# FPGA_IO.net
KiCad netlist of a schematic drawn in Altium Designer
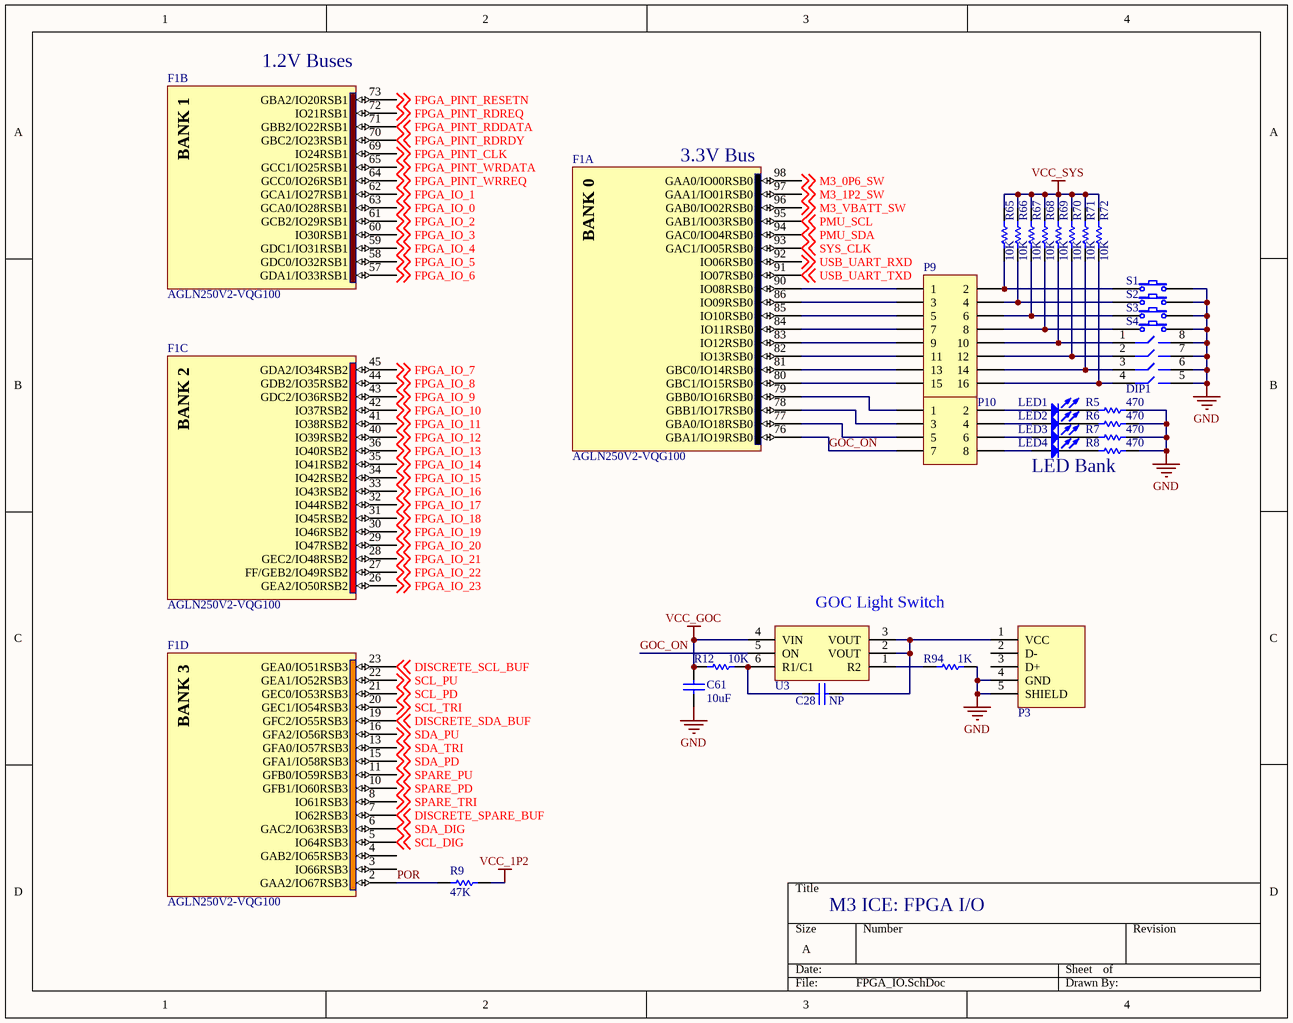
[diagram p0: FPGA_IO.SchDoc]

(export (version "E")
  (design (tool "Eeschema 10.0.6"))
  (components
    (comp (ref "C28")
      (value "NP")
      (footprint "0402")
      (description "Capacitor (Semiconductor SIM Model)")
      (fields (field (name "Comment") "Cap Semi") (field (name "PUBLISHER") "Altium Limited"))
      (libsource (lib "Miscellaneous Devices") (part "Cap Semi"))
    )
    (comp (ref "C61")
      (value "10uF")
      (footprint "0805")
      (description "Capacitor (Semiconductor SIM Model)")
      (fields
        (field (name "DISTPARTNO") "445-6857-1-ND")
        (field (name "MANPARTNO") "C2012X7R1A106K")
        (field (name "PUBLISHER") "Altium Limited")
      )
      (libsource (lib "M3") (part "Cap Chip"))
    )
    (comp (ref "DIP1")
      (value "ADE0404")
      (footprint "DIP-8")
      (description "4-DIP Switch")
      (fields (field (name "DISTPARTNO") "450-1364-ND"))
      (libsource (lib "M3") (part "ADE0404"))
    )
    (comp (ref "F1")
      (value "AGLN250V2-VQG100")
      (footprint "VQ100_N")
      (fields (field (name "DISTPARTNO") "1100-1134-ND") (field (name "PUBLISHER") "Altium Limited"))
      (libsource (lib "Actel IGLOO nano") (part "AGLN250V2-VQG100"))
    )
    (comp (ref "LED1")
      (value "LED 1206")
      (footprint "1206_LED")
      (fields (field (name "DISTPARTNO") "160-1169-1-ND") (field (name "MANPARTNO") "LTST-C150GKT"))
      (libsource (lib "M3") (part "LED 1206"))
    )
    (comp (ref "LED2")
      (value "LED 1206")
      (footprint "1206_LED")
      (fields (field (name "DISTPARTNO") "160-1169-1-ND") (field (name "MANPARTNO") "LTST-C150GKT"))
      (libsource (lib "M3") (part "LED 1206"))
    )
    (comp (ref "LED3")
      (value "LED 1206")
      (footprint "1206_LED")
      (fields (field (name "DISTPARTNO") "160-1169-1-ND") (field (name "MANPARTNO") "LTST-C150GKT"))
      (libsource (lib "M3") (part "LED 1206"))
    )
    (comp (ref "LED4")
      (value "LED 1206")
      (footprint "1206_LED")
      (fields (field (name "DISTPARTNO") "160-1169-1-ND") (field (name "MANPARTNO") "LTST-C150GKT"))
      (libsource (lib "M3") (part "LED 1206"))
    )
    (comp (ref "P3")
      (value "USB_HORIZONTAL")
      (footprint "USB_HORIZONTAL")
      (fields (field (name "DISTPARTNO") "A31726-ND") (field (name "MANPARTNO") "292303-1"))
      (libsource (lib "M3") (part "USB_HORIZONTAL"))
    )
    (comp (ref "P9")
      (value "Header 8X2")
      (footprint "HDR2X8")
      (description "Header, 8-Pin, Dual row")
      (fields (field (name "PUBLISHER") "Altium Limited"))
      (libsource (lib "Miscellaneous Connectors") (part "Header 8X2"))
    )
    (comp (ref "P10")
      (value "Header 4X2")
      (footprint "HDR2X4")
      (description "Header, 4-Pin, Dual row")
      (fields (field (name "PUBLISHER") "Altium Limited"))
      (libsource (lib "Miscellaneous Connectors") (part "Header 4X2"))
    )
    (comp (ref "R5")
      (value "470")
      (footprint "0603")
      (description "Semiconductor Resistor")
      (fields
        (field (name "DISTPARTNO") "P470GCT-ND")
        (field (name "MANPARTNO") "ERJ-3GEYJ471V")
        (field (name "PUBLISHER") "Altium Limited")
      )
      (libsource (lib "M3") (part "Res Chip"))
    )
    (comp (ref "R6")
      (value "470")
      (footprint "0603")
      (description "Semiconductor Resistor")
      (fields
        (field (name "DISTPARTNO") "P470GCT-ND")
        (field (name "MANPARTNO") "ERJ-3GEYJ471V")
        (field (name "PUBLISHER") "Altium Limited")
      )
      (libsource (lib "M3") (part "Res Chip"))
    )
    (comp (ref "R7")
      (value "470")
      (footprint "0603")
      (description "Semiconductor Resistor")
      (fields
        (field (name "DISTPARTNO") "P470GCT-ND")
        (field (name "MANPARTNO") "ERJ-3GEYJ471V")
        (field (name "PUBLISHER") "Altium Limited")
      )
      (libsource (lib "M3") (part "Res Chip"))
    )
    (comp (ref "R8")
      (value "470")
      (footprint "0603")
      (description "Semiconductor Resistor")
      (fields
        (field (name "DISTPARTNO") "P470GCT-ND")
        (field (name "MANPARTNO") "ERJ-3GEYJ471V")
        (field (name "PUBLISHER") "Altium Limited")
      )
      (libsource (lib "M3") (part "Res Chip"))
    )
    (comp (ref "R9")
      (value "47K")
      (footprint "0603")
      (description "Semiconductor Resistor")
      (fields
        (field (name "DISTPARTNO") "P47KGCT-ND")
        (field (name "MANPARTNO") "ERJ-3GEYJ103V")
        (field (name "PUBLISHER") "Altium Limited")
      )
      (libsource (lib "M3") (part "Res Chip"))
    )
    (comp (ref "R12")
      (value "10K")
      (footprint "0402")
      (description "Semiconductor Resistor")
      (fields
        (field (name "MANPARTNO") "ERJ-2RKF1002X")
        (field (name "DISTPARTNO") "P10.0KLCT-ND")
        (field (name "PUBLISHER") "Altium Limited")
      )
      (libsource (lib "M3") (part "Res Chip"))
    )
    (comp (ref "R65")
      (value "10K")
      (footprint "0603")
      (description "Semiconductor Resistor")
      (fields
        (field (name "DISTPARTNO") "P10KGCT-ND")
        (field (name "MANPARTNO") "ERJ-3GEYJ103V")
        (field (name "PUBLISHER") "Altium Limited")
      )
      (libsource (lib "M3") (part "Res Chip"))
    )
    (comp (ref "R66")
      (value "10K")
      (footprint "0603")
      (description "Semiconductor Resistor")
      (fields
        (field (name "DISTPARTNO") "P10KGCT-ND")
        (field (name "MANPARTNO") "ERJ-3GEYJ103V")
        (field (name "PUBLISHER") "Altium Limited")
      )
      (libsource (lib "M3") (part "Res Chip"))
    )
    (comp (ref "R67")
      (value "10K")
      (footprint "0603")
      (description "Semiconductor Resistor")
      (fields
        (field (name "DISTPARTNO") "P10KGCT-ND")
        (field (name "MANPARTNO") "ERJ-3GEYJ103V")
        (field (name "PUBLISHER") "Altium Limited")
      )
      (libsource (lib "M3") (part "Res Chip"))
    )
    (comp (ref "R68")
      (value "10K")
      (footprint "0603")
      (description "Semiconductor Resistor")
      (fields
        (field (name "DISTPARTNO") "P10KGCT-ND")
        (field (name "MANPARTNO") "ERJ-3GEYJ103V")
        (field (name "PUBLISHER") "Altium Limited")
      )
      (libsource (lib "M3") (part "Res Chip"))
    )
    (comp (ref "R69")
      (value "10K")
      (footprint "0603")
      (description "Semiconductor Resistor")
      (fields
        (field (name "DISTPARTNO") "P10KGCT-ND")
        (field (name "MANPARTNO") "ERJ-3GEYJ103V")
        (field (name "PUBLISHER") "Altium Limited")
      )
      (libsource (lib "M3") (part "Res Chip"))
    )
    (comp (ref "R70")
      (value "10K")
      (footprint "0603")
      (description "Semiconductor Resistor")
      (fields
        (field (name "DISTPARTNO") "P10KGCT-ND")
        (field (name "MANPARTNO") "ERJ-3GEYJ103V")
        (field (name "PUBLISHER") "Altium Limited")
      )
      (libsource (lib "M3") (part "Res Chip"))
    )
    (comp (ref "R71")
      (value "10K")
      (footprint "0603")
      (description "Semiconductor Resistor")
      (fields
        (field (name "DISTPARTNO") "P10KGCT-ND")
        (field (name "MANPARTNO") "ERJ-3GEYJ103V")
        (field (name "PUBLISHER") "Altium Limited")
      )
      (libsource (lib "M3") (part "Res Chip"))
    )
    (comp (ref "R72")
      (value "10K")
      (footprint "0603")
      (description "Semiconductor Resistor")
      (fields
        (field (name "DISTPARTNO") "P10KGCT-ND")
        (field (name "MANPARTNO") "ERJ-3GEYJ103V")
        (field (name "PUBLISHER") "Altium Limited")
      )
      (libsource (lib "M3") (part "Res Chip"))
    )
    (comp (ref "R94")
      (value "1K")
      (footprint "0402")
      (description "Semiconductor Resistor")
      (fields
        (field (name "MANPARTNO") "ERJ-2RKF1001X")
        (field (name "DISTPARTNO") "P1.00KLCT-ND")
        (field (name "PUBLISHER") "Altium Limited")
      )
      (libsource (lib "M3") (part "Res Chip"))
    )
    (comp (ref "S1")
      (value "EVQ-PAE04M")
      (footprint "EVQPA")
      (description "Switch Push")
      (fields (field (name "DISTPARTNO") "P8008S-ND"))
      (libsource (lib "M3") (part "EVQ-PAE04M"))
    )
    (comp (ref "S2")
      (value "EVQ-PAE04M")
      (footprint "EVQPA")
      (description "Switch Push")
      (fields (field (name "DISTPARTNO") "P8008S-ND"))
      (libsource (lib "M3") (part "EVQ-PAE04M"))
    )
    (comp (ref "S3")
      (value "EVQ-PAE04M")
      (footprint "EVQPA")
      (description "Switch Push")
      (fields (field (name "DISTPARTNO") "P8008S-ND"))
      (libsource (lib "M3") (part "EVQ-PAE04M"))
    )
    (comp (ref "S4")
      (value "EVQ-PAE04M")
      (footprint "EVQPA")
      (description "Switch Push")
      (fields (field (name "DISTPARTNO") "P8008S-ND"))
      (libsource (lib "M3") (part "EVQ-PAE04M"))
    )
    (comp (ref "U3")
      (value "FDC6330L")
      (footprint "SUPERSOT-6")
      (description "HS Switch")
      (fields (field (name "DISTPARTNO") "FDC6330LCT-ND"))
      (libsource (lib "M3") (part "FDC6330L"))
    )
  )
  (nets
    (net (code "1") (name "/GOC_ON") (class "Default")
      (node (ref "F1") (pin "76") (pinfunction "GBA1/IO19RSB0_76") (pintype "bidirectional"))
      (node (ref "P10") (pin "7") (pinfunction "7_7") (pintype "passive"))
      (node (ref "U3") (pin "5") (pinfunction "ON_5") (pintype "passive"))
    )
    (net (code "2") (name "/POR") (class "Default")
      (node (ref "F1") (pin "2") (pinfunction "GAA2/IO67RSB3_2") (pintype "bidirectional"))
      (node (ref "R9") (pin "1") (pinfunction "1_1") (pintype "passive"))
    )
    (net (code "3") (name "DISCRETE_SCL_BUF") (class "Default")
      (node (ref "F1") (pin "23") (pinfunction "GEA0/IO51RSB3_23") (pintype "bidirectional"))
    )
    (net (code "4") (name "DISCRETE_SDA_BUF") (class "Default")
      (node (ref "F1") (pin "19") (pinfunction "GFC2/IO55RSB3_19") (pintype "bidirectional"))
    )
    (net (code "5") (name "DISCRETE_SPARE_BUF") (class "Default")
      (node (ref "F1") (pin "7") (pinfunction "IO62RSB3_7") (pintype "bidirectional"))
    )
    (net (code "6") (name "FPGA_IO_0") (class "Default")
      (node (ref "F1") (pin "63") (pinfunction "GCA0/IO28RSB1_63") (pintype "bidirectional"))
    )
    (net (code "7") (name "FPGA_IO_1") (class "Default")
      (node (ref "F1") (pin "62") (pinfunction "GCA1/IO27RSB1_62") (pintype "bidirectional"))
    )
    (net (code "8") (name "FPGA_IO_2") (class "Default")
      (node (ref "F1") (pin "61") (pinfunction "GCB2/IO29RSB1_61") (pintype "bidirectional"))
    )
    (net (code "9") (name "FPGA_IO_3") (class "Default")
      (node (ref "F1") (pin "60") (pinfunction "IO30RSB1_60") (pintype "bidirectional"))
    )
    (net (code "10") (name "FPGA_IO_4") (class "Default")
      (node (ref "F1") (pin "59") (pinfunction "GDC1/IO31RSB1_59") (pintype "bidirectional"))
    )
    (net (code "11") (name "FPGA_IO_5") (class "Default")
      (node (ref "F1") (pin "58") (pinfunction "GDC0/IO32RSB1_58") (pintype "bidirectional"))
    )
    (net (code "12") (name "FPGA_IO_6") (class "Default")
      (node (ref "F1") (pin "57") (pinfunction "GDA1/IO33RSB1_57") (pintype "bidirectional"))
    )
    (net (code "13") (name "FPGA_IO_7") (class "Default")
      (node (ref "F1") (pin "45") (pinfunction "GDA2/IO34RSB2_45") (pintype "bidirectional"))
    )
    (net (code "14") (name "FPGA_IO_8") (class "Default")
      (node (ref "F1") (pin "44") (pinfunction "GDB2/IO35RSB2_44") (pintype "bidirectional"))
    )
    (net (code "15") (name "FPGA_IO_9") (class "Default")
      (node (ref "F1") (pin "43") (pinfunction "GDC2/IO36RSB2_43") (pintype "bidirectional"))
    )
    (net (code "16") (name "FPGA_IO_10") (class "Default")
      (node (ref "F1") (pin "42") (pinfunction "IO37RSB2_42") (pintype "bidirectional"))
    )
    (net (code "17") (name "FPGA_IO_11") (class "Default")
      (node (ref "F1") (pin "41") (pinfunction "IO38RSB2_41") (pintype "bidirectional"))
    )
    (net (code "18") (name "FPGA_IO_12") (class "Default")
      (node (ref "F1") (pin "40") (pinfunction "IO39RSB2_40") (pintype "bidirectional"))
    )
    (net (code "19") (name "FPGA_IO_13") (class "Default")
      (node (ref "F1") (pin "36") (pinfunction "IO40RSB2_36") (pintype "bidirectional"))
    )
    (net (code "20") (name "FPGA_IO_14") (class "Default")
      (node (ref "F1") (pin "35") (pinfunction "IO41RSB2_35") (pintype "bidirectional"))
    )
    (net (code "21") (name "FPGA_IO_15") (class "Default")
      (node (ref "F1") (pin "34") (pinfunction "IO42RSB2_34") (pintype "bidirectional"))
    )
    (net (code "22") (name "FPGA_IO_16") (class "Default")
      (node (ref "F1") (pin "33") (pinfunction "IO43RSB2_33") (pintype "bidirectional"))
    )
    (net (code "23") (name "FPGA_IO_17") (class "Default")
      (node (ref "F1") (pin "32") (pinfunction "IO44RSB2_32") (pintype "bidirectional"))
    )
    (net (code "24") (name "FPGA_IO_18") (class "Default")
      (node (ref "F1") (pin "31") (pinfunction "IO45RSB2_31") (pintype "bidirectional"))
    )
    (net (code "25") (name "FPGA_IO_19") (class "Default")
      (node (ref "F1") (pin "30") (pinfunction "IO46RSB2_30") (pintype "bidirectional"))
    )
    (net (code "26") (name "FPGA_IO_20") (class "Default")
      (node (ref "F1") (pin "29") (pinfunction "IO47RSB2_29") (pintype "bidirectional"))
    )
    (net (code "27") (name "FPGA_IO_21") (class "Default")
      (node (ref "F1") (pin "28") (pinfunction "GEC2/IO48RSB2_28") (pintype "bidirectional"))
    )
    (net (code "28") (name "FPGA_IO_22") (class "Default")
      (node (ref "F1") (pin "27") (pinfunction "FF/GEB2/IO49RSB2_27") (pintype "bidirectional"))
    )
    (net (code "29") (name "FPGA_IO_23") (class "Default")
      (node (ref "F1") (pin "26") (pinfunction "GEA2/IO50RSB2_26") (pintype "bidirectional"))
    )
    (net (code "30") (name "FPGA_PINT_CLK") (class "Default")
      (node (ref "F1") (pin "69") (pinfunction "IO24RSB1_69") (pintype "bidirectional"))
    )
    (net (code "31") (name "FPGA_PINT_RDDATA") (class "Default")
      (node (ref "F1") (pin "71") (pinfunction "GBB2/IO22RSB1_71") (pintype "bidirectional"))
    )
    (net (code "32") (name "FPGA_PINT_RDRDY") (class "Default")
      (node (ref "F1") (pin "70") (pinfunction "GBC2/IO23RSB1_70") (pintype "bidirectional"))
    )
    (net (code "33") (name "FPGA_PINT_RDREQ") (class "Default")
      (node (ref "F1") (pin "72") (pinfunction "IO21RSB1_72") (pintype "bidirectional"))
    )
    (net (code "34") (name "FPGA_PINT_RESETN") (class "Default")
      (node (ref "F1") (pin "73") (pinfunction "GBA2/IO20RSB1_73") (pintype "bidirectional"))
    )
    (net (code "35") (name "FPGA_PINT_WRDATA") (class "Default")
      (node (ref "F1") (pin "65") (pinfunction "GCC1/IO25RSB1_65") (pintype "bidirectional"))
    )
    (net (code "36") (name "FPGA_PINT_WRREQ") (class "Default")
      (node (ref "F1") (pin "64") (pinfunction "GCC0/IO26RSB1_64") (pintype "bidirectional"))
    )
    (net (code "37") (name "GND") (class "Default")
      (node (ref "C61") (pin "2") (pinfunction "2_2") (pintype "passive"))
      (node (ref "DIP1") (pin "5") (pinfunction "5_5") (pintype "passive"))
      (node (ref "DIP1") (pin "6") (pinfunction "6_6") (pintype "passive"))
      (node (ref "DIP1") (pin "7") (pinfunction "7_7") (pintype "passive"))
      (node (ref "DIP1") (pin "8") (pinfunction "8_8") (pintype "passive"))
      (node (ref "P3") (pin "4") (pinfunction "GND_4") (pintype "passive"))
      (node (ref "P3") (pin "5") (pinfunction "SHIELD_5") (pintype "passive"))
      (node (ref "R5") (pin "1") (pinfunction "1_1") (pintype "passive"))
      (node (ref "R6") (pin "1") (pinfunction "1_1") (pintype "passive"))
      (node (ref "R7") (pin "1") (pinfunction "1_1") (pintype "passive"))
      (node (ref "R8") (pin "1") (pinfunction "1_1") (pintype "passive"))
      (node (ref "R94") (pin "2") (pinfunction "2_2") (pintype "passive"))
      (node (ref "S1") (pin "2") (pinfunction "2_2") (pintype "passive"))
      (node (ref "S2") (pin "2") (pinfunction "2_2") (pintype "passive"))
      (node (ref "S3") (pin "2") (pinfunction "2_2") (pintype "passive"))
      (node (ref "S4") (pin "2") (pinfunction "2_2") (pintype "passive"))
    )
    (net (code "38") (name "M3_0P6_SW") (class "Default")
      (node (ref "F1") (pin "98") (pinfunction "GAA0/IO00RSB0_98") (pintype "bidirectional"))
    )
    (net (code "39") (name "M3_1P2_SW") (class "Default")
      (node (ref "F1") (pin "97") (pinfunction "GAA1/IO01RSB0_97") (pintype "bidirectional"))
    )
    (net (code "40") (name "M3_VBATT_SW") (class "Default")
      (node (ref "F1") (pin "96") (pinfunction "GAB0/IO02RSB0_96") (pintype "bidirectional"))
    )
    (net (code "41") (name "Net-(DIP1-Pad1)") (class "Default")
      (node (ref "DIP1") (pin "1") (pinfunction "1_1") (pintype "passive"))
      (node (ref "P9") (pin "10") (pinfunction "10_10") (pintype "passive"))
      (node (ref "R69") (pin "2") (pinfunction "2_2") (pintype "passive"))
    )
    (net (code "42") (name "Net-(DIP1-Pad2)") (class "Default")
      (node (ref "DIP1") (pin "2") (pinfunction "2_2") (pintype "passive"))
      (node (ref "P9") (pin "12") (pinfunction "12_12") (pintype "passive"))
      (node (ref "R70") (pin "2") (pinfunction "2_2") (pintype "passive"))
    )
    (net (code "43") (name "Net-(DIP1-Pad3)") (class "Default")
      (node (ref "DIP1") (pin "3") (pinfunction "3_3") (pintype "passive"))
      (node (ref "P9") (pin "14") (pinfunction "14_14") (pintype "passive"))
      (node (ref "R71") (pin "2") (pinfunction "2_2") (pintype "passive"))
    )
    (net (code "44") (name "Net-(DIP1-Pad4)") (class "Default")
      (node (ref "DIP1") (pin "4") (pinfunction "4_4") (pintype "passive"))
      (node (ref "P9") (pin "16") (pinfunction "16_16") (pintype "passive"))
      (node (ref "R72") (pin "2") (pinfunction "2_2") (pintype "passive"))
    )
    (net (code "45") (name "Net-(F1A-GBA0{slash}IO18RSB0)") (class "Default")
      (node (ref "F1") (pin "77") (pinfunction "GBA0/IO18RSB0_77") (pintype "bidirectional"))
      (node (ref "P10") (pin "5") (pinfunction "5_5") (pintype "passive"))
    )
    (net (code "46") (name "Net-(F1A-GBB0{slash}IO16RSB0)") (class "Default")
      (node (ref "F1") (pin "79") (pinfunction "GBB0/IO16RSB0_79") (pintype "bidirectional"))
      (node (ref "P10") (pin "1") (pinfunction "1_1") (pintype "passive"))
    )
    (net (code "47") (name "Net-(F1A-GBB1{slash}IO17RSB0)") (class "Default")
      (node (ref "F1") (pin "78") (pinfunction "GBB1/IO17RSB0_78") (pintype "bidirectional"))
      (node (ref "P10") (pin "3") (pinfunction "3_3") (pintype "passive"))
    )
    (net (code "48") (name "Net-(F1A-GBC0{slash}IO14RSB0)") (class "Default")
      (node (ref "F1") (pin "81") (pinfunction "GBC0/IO14RSB0_81") (pintype "bidirectional"))
      (node (ref "P9") (pin "13") (pinfunction "13_13") (pintype "passive"))
    )
    (net (code "49") (name "Net-(F1A-GBC1{slash}IO15RSB0)") (class "Default")
      (node (ref "F1") (pin "80") (pinfunction "GBC1/IO15RSB0_80") (pintype "bidirectional"))
      (node (ref "P9") (pin "15") (pinfunction "15_15") (pintype "passive"))
    )
    (net (code "50") (name "Net-(F1A-IO08RSB0)") (class "Default")
      (node (ref "F1") (pin "90") (pinfunction "IO08RSB0_90") (pintype "bidirectional"))
      (node (ref "P9") (pin "1") (pinfunction "1_1") (pintype "passive"))
    )
    (net (code "51") (name "Net-(F1A-IO09RSB0)") (class "Default")
      (node (ref "F1") (pin "86") (pinfunction "IO09RSB0_86") (pintype "bidirectional"))
      (node (ref "P9") (pin "3") (pinfunction "3_3") (pintype "passive"))
    )
    (net (code "52") (name "Net-(F1A-IO10RSB0)") (class "Default")
      (node (ref "F1") (pin "85") (pinfunction "IO10RSB0_85") (pintype "bidirectional"))
      (node (ref "P9") (pin "5") (pinfunction "5_5") (pintype "passive"))
    )
    (net (code "53") (name "Net-(F1A-IO11RSB0)") (class "Default")
      (node (ref "F1") (pin "84") (pinfunction "IO11RSB0_84") (pintype "bidirectional"))
      (node (ref "P9") (pin "7") (pinfunction "7_7") (pintype "passive"))
    )
    (net (code "54") (name "Net-(F1A-IO12RSB0)") (class "Default")
      (node (ref "F1") (pin "83") (pinfunction "IO12RSB0_83") (pintype "bidirectional"))
      (node (ref "P9") (pin "9") (pinfunction "9_9") (pintype "passive"))
    )
    (net (code "55") (name "Net-(F1A-IO13RSB0)") (class "Default")
      (node (ref "F1") (pin "82") (pinfunction "IO13RSB0_82") (pintype "bidirectional"))
      (node (ref "P9") (pin "11") (pinfunction "11_11") (pintype "passive"))
    )
    (net (code "56") (name "Net-(LED1-A)") (class "Default")
      (node (ref "LED1") (pin "1") (pinfunction "A_1") (pintype "passive"))
      (node (ref "P10") (pin "2") (pinfunction "2_2") (pintype "passive"))
    )
    (net (code "57") (name "Net-(LED1-K)") (class "Default")
      (node (ref "LED1") (pin "2") (pinfunction "K_2") (pintype "passive"))
      (node (ref "R5") (pin "2") (pinfunction "2_2") (pintype "passive"))
    )
    (net (code "58") (name "Net-(LED2-A)") (class "Default")
      (node (ref "LED2") (pin "1") (pinfunction "A_1") (pintype "passive"))
      (node (ref "P10") (pin "4") (pinfunction "4_4") (pintype "passive"))
    )
    (net (code "59") (name "Net-(LED2-K)") (class "Default")
      (node (ref "LED2") (pin "2") (pinfunction "K_2") (pintype "passive"))
      (node (ref "R6") (pin "2") (pinfunction "2_2") (pintype "passive"))
    )
    (net (code "60") (name "Net-(LED3-A)") (class "Default")
      (node (ref "LED3") (pin "1") (pinfunction "A_1") (pintype "passive"))
      (node (ref "P10") (pin "6") (pinfunction "6_6") (pintype "passive"))
    )
    (net (code "61") (name "Net-(LED3-K)") (class "Default")
      (node (ref "LED3") (pin "2") (pinfunction "K_2") (pintype "passive"))
      (node (ref "R7") (pin "2") (pinfunction "2_2") (pintype "passive"))
    )
    (net (code "62") (name "Net-(LED4-A)") (class "Default")
      (node (ref "LED4") (pin "1") (pinfunction "A_1") (pintype "passive"))
      (node (ref "P10") (pin "8") (pinfunction "8_8") (pintype "passive"))
    )
    (net (code "63") (name "Net-(LED4-K)") (class "Default")
      (node (ref "LED4") (pin "2") (pinfunction "K_2") (pintype "passive"))
      (node (ref "R8") (pin "2") (pinfunction "2_2") (pintype "passive"))
    )
    (net (code "64") (name "Net-(P3-VCC)") (class "Default")
      (node (ref "C28") (pin "1") (pinfunction "1_1") (pintype "passive"))
      (node (ref "P3") (pin "1") (pinfunction "VCC_1") (pintype "passive"))
      (node (ref "U3") (pin "2") (pinfunction "VOUT_2") (pintype "passive"))
      (node (ref "U3") (pin "3") (pinfunction "VOUT_3") (pintype "passive"))
    )
    (net (code "65") (name "Net-(P9-Pad2)") (class "Default")
      (node (ref "P9") (pin "2") (pinfunction "2_2") (pintype "passive"))
      (node (ref "R65") (pin "2") (pinfunction "2_2") (pintype "passive"))
      (node (ref "S1") (pin "1") (pinfunction "1_1") (pintype "passive"))
    )
    (net (code "66") (name "Net-(P9-Pad4)") (class "Default")
      (node (ref "P9") (pin "4") (pinfunction "4_4") (pintype "passive"))
      (node (ref "R66") (pin "2") (pinfunction "2_2") (pintype "passive"))
      (node (ref "S2") (pin "1") (pinfunction "1_1") (pintype "passive"))
    )
    (net (code "67") (name "Net-(P9-Pad6)") (class "Default")
      (node (ref "P9") (pin "6") (pinfunction "6_6") (pintype "passive"))
      (node (ref "R67") (pin "2") (pinfunction "2_2") (pintype "passive"))
      (node (ref "S3") (pin "1") (pinfunction "1_1") (pintype "passive"))
    )
    (net (code "68") (name "Net-(P9-Pad8)") (class "Default")
      (node (ref "P9") (pin "8") (pinfunction "8_8") (pintype "passive"))
      (node (ref "R68") (pin "2") (pinfunction "2_2") (pintype "passive"))
      (node (ref "S4") (pin "1") (pinfunction "1_1") (pintype "passive"))
    )
    (net (code "69") (name "Net-(U3-R1{slash}C1)") (class "Default")
      (node (ref "C28") (pin "2") (pinfunction "2_2") (pintype "passive"))
      (node (ref "R12") (pin "2") (pinfunction "2_2") (pintype "passive"))
      (node (ref "U3") (pin "6") (pinfunction "R1/C1_6") (pintype "passive"))
    )
    (net (code "70") (name "Net-(U3-R2)") (class "Default")
      (node (ref "R94") (pin "1") (pinfunction "1_1") (pintype "passive"))
      (node (ref "U3") (pin "1") (pinfunction "R2_1") (pintype "passive"))
    )
    (net (code "71") (name "PMU_SCL") (class "Default")
      (node (ref "F1") (pin "95") (pinfunction "GAB1/IO03RSB0_95") (pintype "bidirectional"))
    )
    (net (code "72") (name "PMU_SDA") (class "Default")
      (node (ref "F1") (pin "94") (pinfunction "GAC0/IO04RSB0_94") (pintype "bidirectional"))
    )
    (net (code "73") (name "SCL_DIG") (class "Default")
      (node (ref "F1") (pin "5") (pinfunction "IO64RSB3_5") (pintype "bidirectional"))
    )
    (net (code "74") (name "SCL_PD") (class "Default")
      (node (ref "F1") (pin "21") (pinfunction "GEC0/IO53RSB3_21") (pintype "bidirectional"))
    )
    (net (code "75") (name "SCL_PU") (class "Default")
      (node (ref "F1") (pin "22") (pinfunction "GEA1/IO52RSB3_22") (pintype "bidirectional"))
    )
    (net (code "76") (name "SCL_TRI") (class "Default")
      (node (ref "F1") (pin "20") (pinfunction "GEC1/IO54RSB3_20") (pintype "bidirectional"))
    )
    (net (code "77") (name "SDA_DIG") (class "Default")
      (node (ref "F1") (pin "6") (pinfunction "GAC2/IO63RSB3_6") (pintype "bidirectional"))
    )
    (net (code "78") (name "SDA_PD") (class "Default")
      (node (ref "F1") (pin "15") (pinfunction "GFA1/IO58RSB3_15") (pintype "bidirectional"))
    )
    (net (code "79") (name "SDA_PU") (class "Default")
      (node (ref "F1") (pin "16") (pinfunction "GFA2/IO56RSB3_16") (pintype "bidirectional"))
    )
    (net (code "80") (name "SDA_TRI") (class "Default")
      (node (ref "F1") (pin "13") (pinfunction "GFA0/IO57RSB3_13") (pintype "bidirectional"))
    )
    (net (code "81") (name "SPARE_PD") (class "Default")
      (node (ref "F1") (pin "10") (pinfunction "GFB1/IO60RSB3_10") (pintype "bidirectional"))
    )
    (net (code "82") (name "SPARE_PU") (class "Default")
      (node (ref "F1") (pin "11") (pinfunction "GFB0/IO59RSB3_11") (pintype "bidirectional"))
    )
    (net (code "83") (name "SPARE_TRI") (class "Default")
      (node (ref "F1") (pin "8") (pinfunction "IO61RSB3_8") (pintype "bidirectional"))
    )
    (net (code "84") (name "SYS_CLK") (class "Default")
      (node (ref "F1") (pin "93") (pinfunction "GAC1/IO05RSB0_93") (pintype "bidirectional"))
    )
    (net (code "85") (name "USB_UART_RXD") (class "Default")
      (node (ref "F1") (pin "92") (pinfunction "IO06RSB0_92") (pintype "bidirectional"))
    )
    (net (code "86") (name "USB_UART_TXD") (class "Default")
      (node (ref "F1") (pin "91") (pinfunction "IO07RSB0_91") (pintype "bidirectional"))
    )
    (net (code "87") (name "VCC_1P2") (class "Default")
      (node (ref "R9") (pin "2") (pinfunction "2_2") (pintype "passive"))
    )
    (net (code "88") (name "VCC_GOC") (class "Default")
      (node (ref "C61") (pin "1") (pinfunction "1_1") (pintype "passive"))
      (node (ref "R12") (pin "1") (pinfunction "1_1") (pintype "passive"))
      (node (ref "U3") (pin "4") (pinfunction "VIN_4") (pintype "passive"))
    )
    (net (code "89") (name "VCC_SYS") (class "Default")
      (node (ref "R65") (pin "1") (pinfunction "1_1") (pintype "passive"))
      (node (ref "R66") (pin "1") (pinfunction "1_1") (pintype "passive"))
      (node (ref "R67") (pin "1") (pinfunction "1_1") (pintype "passive"))
      (node (ref "R68") (pin "1") (pinfunction "1_1") (pintype "passive"))
      (node (ref "R69") (pin "1") (pinfunction "1_1") (pintype "passive"))
      (node (ref "R70") (pin "1") (pinfunction "1_1") (pintype "passive"))
      (node (ref "R71") (pin "1") (pinfunction "1_1") (pintype "passive"))
      (node (ref "R72") (pin "1") (pinfunction "1_1") (pintype "passive"))
    )
    (net (code "90") (name "unconnected-(F1D-GAB2{slash}IO65RSB3-Pad4)") (class "Default")
      (node (ref "F1") (pin "4") (pinfunction "GAB2/IO65RSB3_4") (pintype "bidirectional"))
    )
    (net (code "91") (name "unconnected-(F1D-IO66RSB3-Pad3)") (class "Default")
      (node (ref "F1") (pin "3") (pinfunction "IO66RSB3_3") (pintype "bidirectional"))
    )
    (net (code "92") (name "unconnected-(P3-D+-Pad3)") (class "Default")
      (node (ref "P3") (pin "3") (pinfunction "D+_3") (pintype "passive"))
    )
    (net (code "93") (name "unconnected-(P3-D--Pad2)") (class "Default")
      (node (ref "P3") (pin "2") (pinfunction "D-_2") (pintype "passive"))
    )
  )
)
